# esquematicoSolenoide.net
KiCad netlist of a schematic drawn in Altium Designer
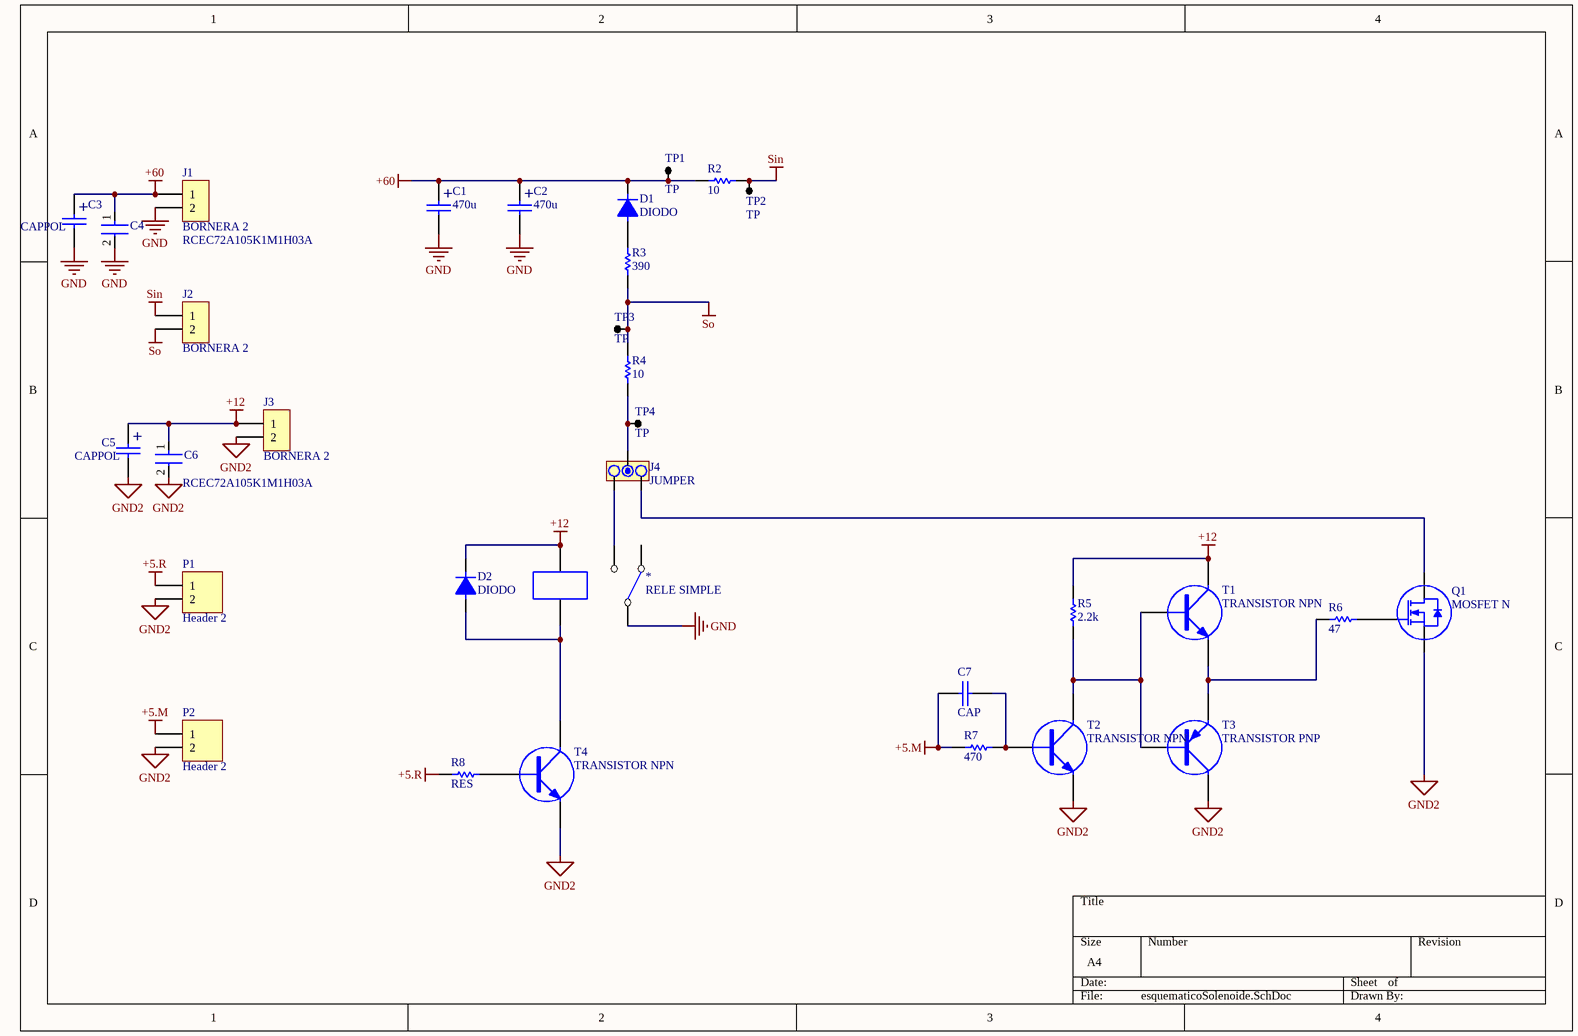
[diagram p0: esquematicoSolenoide.SchDoc]

(export (version "E")
  (design (tool "Eeschema 10.0.6"))
  (components
    (comp (ref "*")
      (value "RELE SIMPLE")
      (footprint "RELE SERIE 964")
      (libsource (lib "LIB PIO IX") (part "RELE SIMPLE"))
    )
    (comp (ref "C1") (value "470u") (footprint "CAP300RP") (libsource (lib "LIB PIO IX") (part "CAPPOL")))
    (comp (ref "C2") (value "470u") (footprint "CAP300RP") (libsource (lib "LIB PIO IX") (part "CAPPOL")))
    (comp (ref "C3") (value "CAPPOL") (footprint "CAP100RP") (libsource (lib "LIB PIO IX") (part "CAPPOL")))
    (comp (ref "C4")
      (value "RCEC72A105K1M1H03A")
      (footprint "FP-RCE1M1-MFG")
      (fields (field (name "TOLERANCE") "10%"))
      (libsource (lib "Altium Content Vault") (part "RCEC72A105K1M1H03A"))
    )
    (comp (ref "C5") (value "CAPPOL") (footprint "CAP100RP") (libsource (lib "LIB PIO IX") (part "CAPPOL")))
    (comp (ref "C6")
      (value "RCEC72A105K1M1H03A")
      (footprint "FP-RCE1M1-MFG")
      (fields (field (name "TOLERANCE") "10%"))
      (libsource (lib "Altium Content Vault") (part "RCEC72A105K1M1H03A"))
    )
    (comp (ref "C7") (value "CAP") (footprint "CAP200") (libsource (lib "LIBEBAL") (part "CAP")))
    (comp (ref "D1") (value "DIODO") (footprint "DO41") (libsource (lib "LIB PIO IX") (part "DIODO")))
    (comp (ref "D2") (value "DIODO") (footprint "DO41") (libsource (lib "LIB PIO IX") (part "DIODO")))
    (comp (ref "J1")
      (value "BORNERA 2")
      (footprint "BORNERA2")
      (libsource (lib "LIB PIO IX") (part "BORNERA 2"))
    )
    (comp (ref "J2")
      (value "BORNERA 2")
      (footprint "BORNERA2")
      (libsource (lib "LIB PIO IX") (part "BORNERA 2"))
    )
    (comp (ref "J3")
      (value "BORNERA 2")
      (footprint "BORNERA2")
      (libsource (lib "LIB PIO IX") (part "BORNERA 2"))
    )
    (comp (ref "J4") (value "JUMPER") (footprint "JUMPER3") (libsource (lib "LIB PIO IX") (part "JUMPER3")))
    (comp (ref "P1")
      (value "Header 2")
      (footprint "HDR1X2")
      (description "Header, 2-Pin")
      (fields (field (name "PUBLISHER") "Altium Limited"))
      (libsource (lib "Miscellaneous Connectors") (part "Header 2"))
    )
    (comp (ref "P2")
      (value "Header 2")
      (footprint "HDR1X2")
      (description "Header, 2-Pin")
      (fields (field (name "PUBLISHER") "Altium Limited"))
      (libsource (lib "Miscellaneous Connectors") (part "Header 2"))
    )
    (comp (ref "Q1") (value "MOSFET N") (footprint "TO-220 V") (libsource (lib "LIBEBAL") (part "MOSFET N")))
    (comp (ref "R2") (value "10") (footprint "RES400") (libsource (lib "LIB PIO IX") (part "RES")))
    (comp (ref "R3") (value "390") (footprint "RES400") (libsource (lib "LIB PIO IX") (part "RES")))
    (comp (ref "R4") (value "10") (footprint "RES400") (libsource (lib "LIB PIO IX") (part "RES")))
    (comp (ref "R5") (value "2.2k") (footprint "RES400") (libsource (lib "LIB PIO IX") (part "RES")))
    (comp (ref "R6") (value "47") (footprint "RES400") (libsource (lib "LIB PIO IX") (part "RES")))
    (comp (ref "R7") (value "470") (footprint "RES400") (libsource (lib "LIB PIO IX") (part "RES")))
    (comp (ref "R8") (value "RES") (footprint "RES400") (libsource (lib "LIB PIO IX") (part "RES")))
    (comp (ref "T1")
      (value "TRANSISTOR NPN")
      (footprint "TO92")
      (libsource (lib "LIBEBAL") (part "TRANSISTOR NPN"))
    )
    (comp (ref "T2")
      (value "TRANSISTOR NPN")
      (footprint "TO92")
      (libsource (lib "LIBEBAL") (part "TRANSISTOR NPN"))
    )
    (comp (ref "T3")
      (value "TRANSISTOR PNP")
      (footprint "TO92")
      (libsource (lib "LIBEBAL") (part "TRANSISTOR PNP"))
    )
    (comp (ref "T4")
      (value "TRANSISTOR NPN")
      (footprint "TO92")
      (libsource (lib "LIBEBAL") (part "TRANSISTOR NPN"))
    )
    (comp (ref "TP1") (value "TP") (footprint "TPTH") (libsource (lib "LIB PIO IX") (part "TP")))
    (comp (ref "TP2") (value "TP") (footprint "TPTH") (libsource (lib "LIB PIO IX") (part "TP")))
    (comp (ref "TP3") (value "TP") (footprint "TPTH") (libsource (lib "LIB PIO IX") (part "TP")))
    (comp (ref "TP4") (value "TP") (footprint "TPTH") (libsource (lib "LIB PIO IX") (part "TP")))
  )
  (nets
    (net (code "1") (name "+5.M") (class "Default")
      (node (ref "C7") (pin "1") (pinfunction "1_1") (pintype "passive"))
      (node (ref "P2") (pin "1") (pinfunction "1_1") (pintype "passive"))
      (node (ref "R7") (pin "1") (pinfunction "1_1") (pintype "passive"))
    )
    (net (code "2") (name "+5.R") (class "Default")
      (node (ref "P1") (pin "1") (pinfunction "1_1") (pintype "passive"))
      (node (ref "R8") (pin "2") (pinfunction "2_2") (pintype "passive"))
    )
    (net (code "3") (name "+12") (class "Default")
      (node (ref "*") (pin "B1") (pinfunction "B1_B1") (pintype "passive"))
      (node (ref "C5") (pin "1") (pinfunction "1_1") (pintype "passive"))
      (node (ref "C6") (pin "1") (pinfunction "1_1") (pintype "passive"))
      (node (ref "D2") (pin "2") (pinfunction "2_2") (pintype "passive"))
      (node (ref "J3") (pin "1") (pinfunction "1_1") (pintype "passive"))
      (node (ref "R5") (pin "1") (pinfunction "1_1") (pintype "passive"))
      (node (ref "T1") (pin "2") (pinfunction "C_2") (pintype "passive"))
    )
    (net (code "4") (name "+60") (class "Default")
      (node (ref "C1") (pin "1") (pinfunction "1_1") (pintype "passive"))
      (node (ref "C2") (pin "1") (pinfunction "1_1") (pintype "passive"))
      (node (ref "C3") (pin "1") (pinfunction "1_1") (pintype "passive"))
      (node (ref "C4") (pin "1") (pinfunction "1_1") (pintype "passive"))
      (node (ref "D1") (pin "2") (pinfunction "2_2") (pintype "passive"))
      (node (ref "J1") (pin "1") (pinfunction "1_1") (pintype "passive"))
      (node (ref "R2") (pin "1") (pinfunction "1_1") (pintype "passive"))
      (node (ref "TP1") (pin "1") (pinfunction "1_1") (pintype "passive"))
    )
    (net (code "5") (name "GND") (class "Default")
      (node (ref "*") (pin "C1") (pinfunction "C1_C1") (pintype "passive"))
      (node (ref "C1") (pin "2") (pinfunction "2_2") (pintype "passive"))
      (node (ref "C2") (pin "2") (pinfunction "2_2") (pintype "passive"))
      (node (ref "C3") (pin "2") (pinfunction "2_2") (pintype "passive"))
      (node (ref "C4") (pin "2") (pinfunction "2_2") (pintype "passive"))
      (node (ref "J1") (pin "2") (pinfunction "2_2") (pintype "passive"))
    )
    (net (code "6") (name "GND2") (class "Default")
      (node (ref "C5") (pin "2") (pinfunction "2_2") (pintype "passive"))
      (node (ref "C6") (pin "2") (pinfunction "2_2") (pintype "passive"))
      (node (ref "J3") (pin "2") (pinfunction "2_2") (pintype "passive"))
      (node (ref "P1") (pin "2") (pinfunction "2_2") (pintype "passive"))
      (node (ref "P2") (pin "2") (pinfunction "2_2") (pintype "passive"))
      (node (ref "Q1") (pin "3") (pinfunction "S_3") (pintype "passive"))
      (node (ref "T2") (pin "3") (pinfunction "E_3") (pintype "passive"))
      (node (ref "T3") (pin "2") (pinfunction "C_2") (pintype "passive"))
      (node (ref "T4") (pin "3") (pinfunction "E_3") (pintype "passive"))
    )
    (net (code "7") (name "Net-(*-PadNA1)") (class "Default")
      (node (ref "*") (pin "NA1") (pinfunction "NA1_NA1") (pintype "passive"))
      (node (ref "J4") (pin "3") (pinfunction "3_3") (pintype "passive"))
    )
    (net (code "8") (name "Net-(D1-Pad1)") (class "Default")
      (node (ref "D1") (pin "1") (pinfunction "1_1") (pintype "passive"))
      (node (ref "R3") (pin "2") (pinfunction "2_2") (pintype "passive"))
    )
    (net (code "9") (name "Net-(J4-Pad2)") (class "Default")
      (node (ref "J4") (pin "2") (pinfunction "2_2") (pintype "passive"))
      (node (ref "R4") (pin "1") (pinfunction "1_1") (pintype "passive"))
      (node (ref "TP4") (pin "1") (pinfunction "1_1") (pintype "passive"))
    )
    (net (code "10") (name "Net-(Q1-D)") (class "Default")
      (node (ref "J4") (pin "1") (pinfunction "1_1") (pintype "passive"))
      (node (ref "Q1") (pin "2") (pinfunction "D_2") (pintype "passive"))
    )
    (net (code "11") (name "Net-(Q1-G)") (class "Default")
      (node (ref "Q1") (pin "1") (pinfunction "G_1") (pintype "passive"))
      (node (ref "R6") (pin "1") (pinfunction "1_1") (pintype "passive"))
    )
    (net (code "12") (name "Net-(T1-B)") (class "Default")
      (node (ref "R5") (pin "2") (pinfunction "2_2") (pintype "passive"))
      (node (ref "T1") (pin "1") (pinfunction "B_1") (pintype "passive"))
      (node (ref "T2") (pin "2") (pinfunction "C_2") (pintype "passive"))
      (node (ref "T3") (pin "1") (pinfunction "B_1") (pintype "passive"))
    )
    (net (code "13") (name "Net-(T1-E)") (class "Default")
      (node (ref "R6") (pin "2") (pinfunction "2_2") (pintype "passive"))
      (node (ref "T1") (pin "3") (pinfunction "E_3") (pintype "passive"))
      (node (ref "T3") (pin "3") (pinfunction "E_3") (pintype "passive"))
    )
    (net (code "14") (name "Net-(T2-B)") (class "Default")
      (node (ref "C7") (pin "2") (pinfunction "2_2") (pintype "passive"))
      (node (ref "R7") (pin "2") (pinfunction "2_2") (pintype "passive"))
      (node (ref "T2") (pin "1") (pinfunction "B_1") (pintype "passive"))
    )
    (net (code "15") (name "Net-(T4-B)") (class "Default")
      (node (ref "R8") (pin "1") (pinfunction "1_1") (pintype "passive"))
      (node (ref "T4") (pin "1") (pinfunction "B_1") (pintype "passive"))
    )
    (net (code "16") (name "Net-(T4-C)") (class "Default")
      (node (ref "*") (pin "B2") (pinfunction "B2_B2") (pintype "passive"))
      (node (ref "D2") (pin "1") (pinfunction "1_1") (pintype "passive"))
      (node (ref "T4") (pin "2") (pinfunction "C_2") (pintype "passive"))
    )
    (net (code "17") (name "Sin") (class "Default")
      (node (ref "J2") (pin "1") (pinfunction "1_1") (pintype "passive"))
      (node (ref "R2") (pin "2") (pinfunction "2_2") (pintype "passive"))
      (node (ref "TP2") (pin "1") (pinfunction "1_1") (pintype "passive"))
    )
    (net (code "18") (name "So") (class "Default")
      (node (ref "J2") (pin "2") (pinfunction "2_2") (pintype "passive"))
      (node (ref "R3") (pin "1") (pinfunction "1_1") (pintype "passive"))
      (node (ref "R4") (pin "2") (pinfunction "2_2") (pintype "passive"))
      (node (ref "TP3") (pin "1") (pinfunction "1_1") (pintype "passive"))
    )
    (net (code "19") (name "unconnected-(*-PadNC1)") (class "Default")
      (node (ref "*") (pin "NC1") (pinfunction "NC1_NC1") (pintype "passive"))
    )
  )
)
